# v2_1.net
KiCad netlist of a schematic drawn in EAGLE
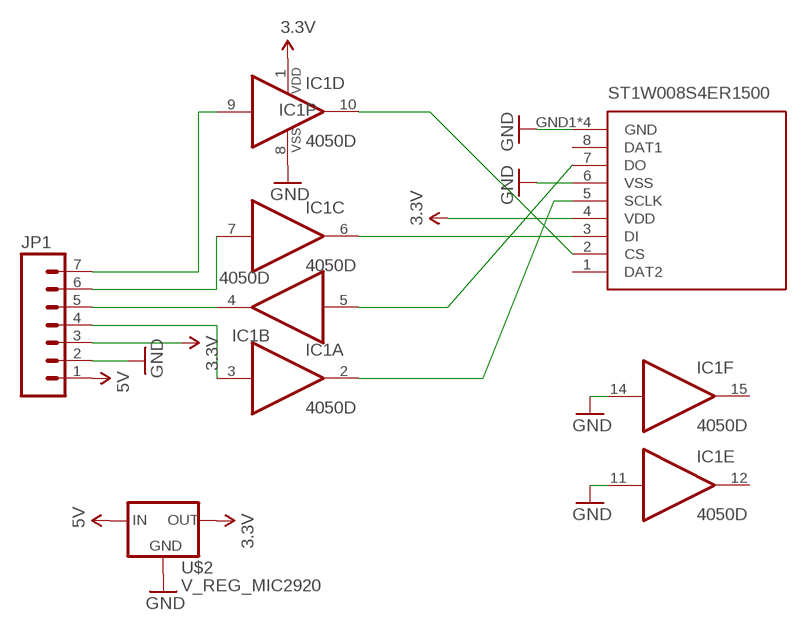
[diagram p0: schematic, sheet 1]

(export (version "E")
  (design (tool "Eeschema 10.0.6"))
  (components
    (comp (ref "IC1")
      (value "4050D")
      (footprint "eagle-import:SO16")
      (libsource (lib "eagle-import") (part "4050D"))
    )
    (comp (ref "JP1")
      (value "M07")
      (footprint "eagle-import:1X07")
      (libsource (lib "eagle-import") (part "M07"))
    )
    (comp (ref "U$1")
      (value "ST1W008S4ER1500")
      (footprint "eagle-import:ST1W008S4ER1500")
      (libsource (lib "eagle-import") (part "ST1W008S4ER1500"))
    )
    (comp (ref "U$2")
      (value "V_REG_MIC2920")
      (footprint "eagle-import:SOT223")
      (libsource (lib "eagle-import") (part "V_REG_MIC2920"))
    )
  )
  (nets
    (net (code "1") (name "3.3V") (class "Default")
      (node (ref "IC1") (pin "1") (pinfunction "VDD_1") (pintype "power_in"))
      (node (ref "JP1") (pin "3") (pinfunction "3_3") (pintype "passive"))
      (node (ref "U$1") (pin "4") (pinfunction "VDD_4") (pintype "bidirectional"))
      (node (ref "U$2") (pin "3") (pinfunction "OUT_3") (pintype "passive"))
    )
    (net (code "2") (name "5V") (class "Default")
      (node (ref "JP1") (pin "1") (pinfunction "1_1") (pintype "passive"))
      (node (ref "U$2") (pin "1") (pinfunction "IN_1") (pintype "input"))
    )
    (net (code "3") (name "GND") (class "Default")
      (node (ref "IC1") (pin "11") (pinfunction "I_11") (pintype "input"))
      (node (ref "IC1") (pin "14") (pinfunction "I_14") (pintype "input"))
      (node (ref "IC1") (pin "8") (pinfunction "VSS_8") (pintype "power_in"))
      (node (ref "JP1") (pin "2") (pinfunction "2_2") (pintype "passive"))
      (node (ref "U$1") (pin "6") (pinfunction "VSS_6") (pintype "bidirectional"))
      (node (ref "U$1") (pin "GND1") (pinfunction "GND_GND1") (pintype "bidirectional"))
      (node (ref "U$1") (pin "GND2") (pinfunction "GND_GND2") (pintype "bidirectional"))
      (node (ref "U$1") (pin "GND3") (pinfunction "GND_GND3") (pintype "bidirectional"))
      (node (ref "U$1") (pin "GND4") (pinfunction "GND_GND4") (pintype "bidirectional"))
      (node (ref "U$2") (pin "2") (pinfunction "GND_2") (pintype "input"))
    )
    (net (code "4") (name "Net-(IC1A-I)") (class "Default")
      (node (ref "IC1") (pin "3") (pinfunction "I_3") (pintype "input"))
      (node (ref "JP1") (pin "4") (pinfunction "4_4") (pintype "passive"))
    )
    (net (code "5") (name "Net-(IC1A-O)") (class "Default")
      (node (ref "IC1") (pin "2") (pinfunction "O_2") (pintype "output"))
      (node (ref "U$1") (pin "5") (pinfunction "SCLK_5") (pintype "bidirectional"))
    )
    (net (code "6") (name "Net-(IC1B-I)") (class "Default")
      (node (ref "IC1") (pin "5") (pinfunction "I_5") (pintype "input"))
      (node (ref "U$1") (pin "7") (pinfunction "DO_7") (pintype "bidirectional"))
    )
    (net (code "7") (name "Net-(IC1B-O)") (class "Default")
      (node (ref "IC1") (pin "4") (pinfunction "O_4") (pintype "output"))
      (node (ref "JP1") (pin "5") (pinfunction "5_5") (pintype "passive"))
    )
    (net (code "8") (name "Net-(IC1C-I)") (class "Default")
      (node (ref "IC1") (pin "7") (pinfunction "I_7") (pintype "input"))
      (node (ref "JP1") (pin "6") (pinfunction "6_6") (pintype "passive"))
    )
    (net (code "9") (name "Net-(IC1C-O)") (class "Default")
      (node (ref "IC1") (pin "6") (pinfunction "O_6") (pintype "output"))
      (node (ref "U$1") (pin "3") (pinfunction "DI_3") (pintype "bidirectional"))
    )
    (net (code "10") (name "Net-(IC1D-I)") (class "Default")
      (node (ref "IC1") (pin "9") (pinfunction "I_9") (pintype "input"))
      (node (ref "JP1") (pin "7") (pinfunction "7_7") (pintype "passive"))
    )
    (net (code "11") (name "Net-(IC1D-O)") (class "Default")
      (node (ref "IC1") (pin "10") (pinfunction "O_10") (pintype "output"))
      (node (ref "U$1") (pin "2") (pinfunction "CS_2") (pintype "bidirectional"))
    )
    (net (code "12") (name "unconnected-(IC1E-O-Pad12)") (class "Default")
      (node (ref "IC1") (pin "12") (pinfunction "O_12") (pintype "output"))
    )
    (net (code "13") (name "unconnected-(IC1F-O-Pad15)") (class "Default")
      (node (ref "IC1") (pin "15") (pinfunction "O_15") (pintype "output"))
    )
    (net (code "14") (name "unconnected-(U$1-DAT1-Pad8)") (class "Default")
      (node (ref "U$1") (pin "8") (pinfunction "DAT1_8") (pintype "bidirectional"))
    )
    (net (code "15") (name "unconnected-(U$1-DAT2-Pad1)") (class "Default")
      (node (ref "U$1") (pin "1") (pinfunction "DAT2_1") (pintype "bidirectional"))
    )
  )
)
